# 3V3Primary.net
KiCad netlist of a schematic drawn in Altium Designer
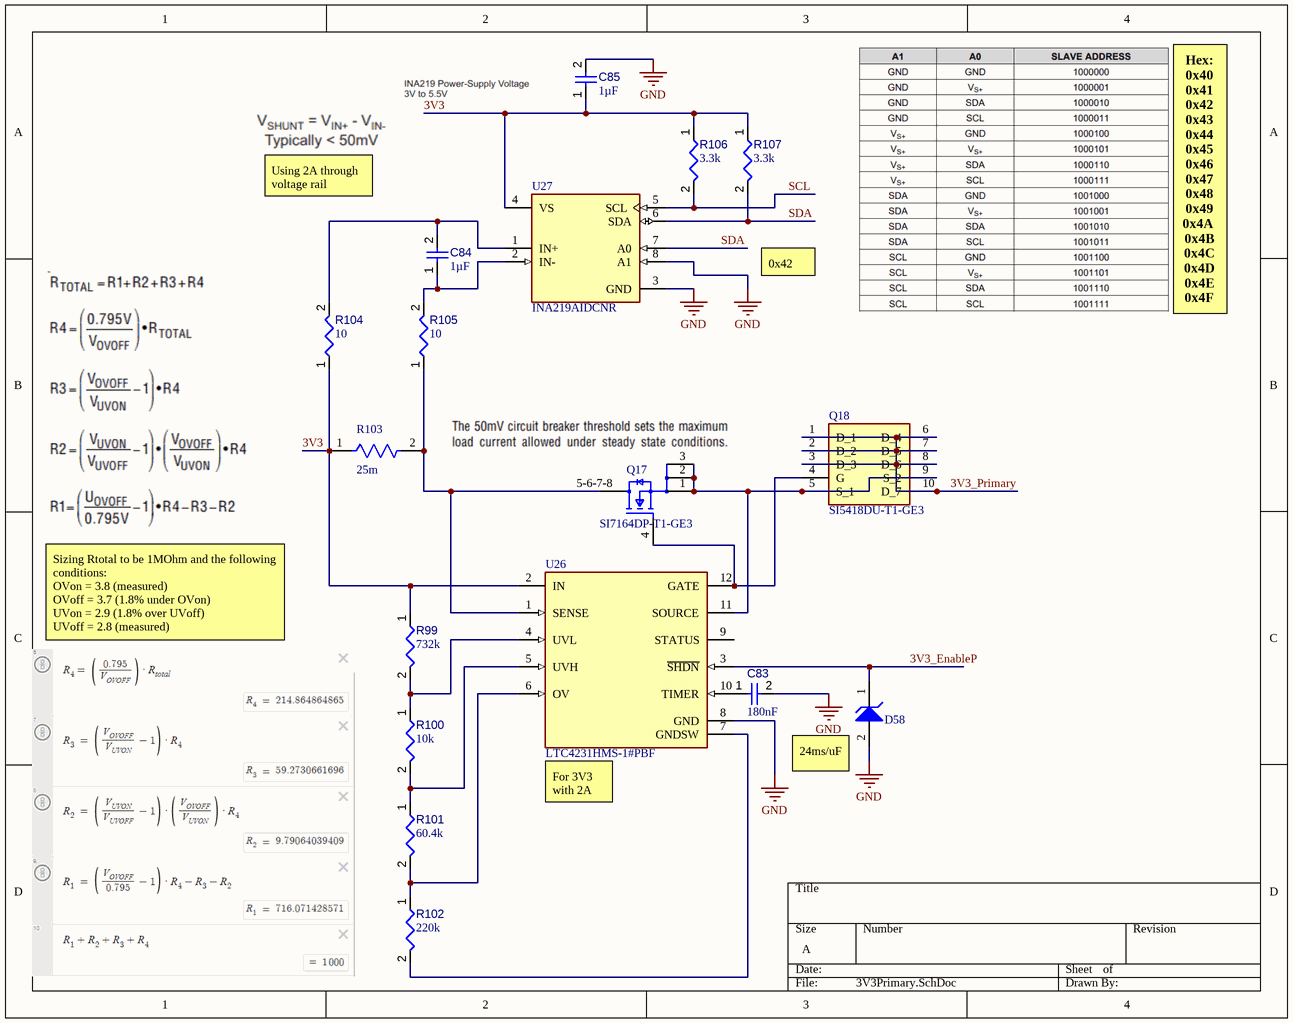
[diagram p0: 3V3Primary.SchDoc]

(export (version "E")
  (design (tool "Eeschema 10.0.6"))
  (components
    (comp (ref "C83")
      (value "180nF")
      (footprint "FP-C0805C-DN-IPC_A")
      (fields (field (name "Comment") "C0805C184K5RACTU"))
      (libsource (lib "UGA SSRL Hardware Team") (part "CAP-NP-2"))
    )
    (comp (ref "C84")
      (value "1µF")
      (footprint "CAPC1608X90X40LL10T20")
      (description "Chip Capacitor, 1 uF, +/- 10%, 25 V, 0603 (1608 Metric)")
      (fields (field (name "TOLERANCE") "10%") (field (name "Comment") "Capacitor 1 uF +/- 10% 25 V 0603"))
      (libsource (lib "UGA SSRL Hardware Team") (part "CAP-NP-2"))
    )
    (comp (ref "C85")
      (value "1µF")
      (footprint "CAPC1608X90X35ML15T15")
      (description "Chip Capacitor, 1 uF, +/- 10%, 16 V, 0603 (1608 Metric)")
      (fields (field (name "TOLERANCE") "10%") (field (name "Comment") "Capacitor 1uF +/- 10% 16V 0603"))
      (libsource (lib "UGA SSRL Hardware Team") (part "CAP-NP-2"))
    )
    (comp (ref "D58")
      (value "MM3Z3V6T1G")
      (footprint "ONSC-SOD-323-2-477-02_V")
      (description "Zener Voltage Regulator, 300 mW, 2-Pin SOD-323, Pb-Free, Tape and Reel")
      (fields (field (name "MANUFACTURER") "On Semiconductor"))
      (libsource (lib "Altium Content Vault") (part "ONSC-K1A2-2"))
    )
    (comp (ref "Q17")
      (value "SI7164DP-T1-GE3")
      (footprint "Vishay_S17-0173-SINGLE_MFG")
      (libsource (lib "UGA SSRL Hardware Team") (part "SI7164DP-T1-GE3"))
    )
    (comp (ref "Q18")
      (value "SI5418DU-T1-GE3")
      (footprint "SI5418DU-T1-GE3-Footprint-1")
      (libsource (lib "UGA SSRL Hardware Team") (part "SI5418DU-T1-GE3-Symbol-1"))
    )
    (comp (ref "R99")
      (value "732k")
      (footprint "FP-CR0805-IPC_A")
      (fields
        (field (name "POWER") "125mW")
        (field (name "TOLERANCE") "1%")
        (field (name "Comment") "CR0805-FX-7323ELF")
      )
      (libsource (lib "UGA SSRL Hardware Team") (part "RES-2"))
    )
    (comp (ref "R100")
      (value "10k")
      (footprint "RESC1005X40X25ML05T05")
      (description "Chip Resistor, 10 KOhm, +/- 1%, 0.1 W, -55 to 155 degC, 0402 (1005 Metric)")
      (fields (field (name "TOLERANCE") "1%") (field (name "POWER") "100mW"))
      (libsource (lib "UGA SSRL Hardware Team") (part "RES-2"))
    )
    (comp (ref "R101")
      (value "60.4k")
      (footprint "RESC1005X40X25NL05T10")
      (fields
        (field (name "TOLERANCE") "1%")
        (field (name "POWER") "62.5mW")
        (field (name "Comment") "RC0402FR-0760K4L")
      )
      (libsource (lib "UGA SSRL Hardware Team") (part "RES-2"))
    )
    (comp (ref "R102")
      (value "220k")
      (footprint "FP-ESR01-IPC_C")
      (fields
        (field (name "POWER") "200mW")
        (field (name "TOLERANCE") "5%")
        (field (name "Comment") "ESR01MZPJ224")
      )
      (libsource (lib "UGA SSRL Hardware Team") (part "RES-2"))
    )
    (comp (ref "R103")
      (value "CSR1206FK25L0")
      (footprint "FP-CSR1206-IPC_C")
      (description "General Purpose Thick Film Chip Resistor, 1206, 25mΩ, 1%, 0.5W")
      (fields (field (name "RESISTANCE") "25m") (field (name "TOLERANCE") "1%"))
      (libsource (lib "Altium Content Vault") (part "1029c3af85768c4190bb7ad29bc67b5"))
    )
    (comp (ref "R104")
      (value "10")
      (footprint "RESC0402(1005)_L")
      (description "Chip Resistor, 10 Ohms, +/-1 %, 63 mW, -55 to 155 degC, 0402")
      (fields (field (name "TOLERANCE") "1%") (field (name "POWER") "63mW"))
      (libsource (lib "UGA SSRL Hardware Team") (part "RES-2"))
    )
    (comp (ref "R105")
      (value "10")
      (footprint "RESC0402(1005)_L")
      (description "Chip Resistor, 10 Ohms, +/-1 %, 63 mW, -55 to 155 degC, 0402")
      (fields (field (name "TOLERANCE") "1%") (field (name "POWER") "63mW"))
      (libsource (lib "UGA SSRL Hardware Team") (part "RES-2"))
    )
    (comp (ref "R106")
      (value "3.3k")
      (footprint "FP-CRCW1210-e3-IPC_C")
      (fields
        (field (name "TOLERANCE") "5%")
        (field (name "POWER") "500mW")
        (field (name "Comment") "CRCW12103K30JNEA")
      )
      (libsource (lib "UGA SSRL Hardware Team") (part "RES-2"))
    )
    (comp (ref "R107")
      (value "3.3k")
      (footprint "FP-CRCW1210-e3-IPC_C")
      (fields
        (field (name "TOLERANCE") "5%")
        (field (name "POWER") "500mW")
        (field (name "Comment") "CRCW12103K30JNEA")
      )
      (libsource (lib "UGA SSRL Hardware Team") (part "RES-2"))
    )
    (comp (ref "U26")
      (value "LTC4231HMS-1#PBF")
      (footprint "FP-MS-12-05-08-1668-MFG")
      (description "IC HOT SWAP CTRLR GP 12MSOP")
      (libsource (lib "Altium Content Vault") (part "22a006f8750c3b6cd4295fbd2c2f62c"))
    )
    (comp (ref "U27")
      (value "INA219AIDCNR")
      (footprint "FP-DCN0008A-IPC_A")
      (description "Power Supply Support Circuit, Fixed, 2 Channel, 2V, PDSO8")
      (libsource (lib "UGA SSRL Hardware Team") (part "e16934b8ef90d0e345b266f0ae9cd81"))
    )
  )
  (nets
    (net (code "1") (name "/3V3") (class "Default")
      (node (ref "C85") (pin "1") (pinfunction "1_1") (pintype "passive"))
      (node (ref "R103") (pin "1") (pinfunction "1_1") (pintype "passive"))
      (node (ref "R104") (pin "1") (pinfunction "1_1") (pintype "passive"))
      (node (ref "R106") (pin "1") (pinfunction "1_1") (pintype "passive"))
      (node (ref "R107") (pin "1") (pinfunction "1_1") (pintype "passive"))
      (node (ref "R99") (pin "1") (pinfunction "1_1") (pintype "passive"))
      (node (ref "U26") (pin "2") (pinfunction "IN_2") (pintype "power_in"))
      (node (ref "U27") (pin "4") (pinfunction "VS_4") (pintype "power_in"))
    )
    (net (code "2") (name "/3V3_EnableP") (class "Default")
      (node (ref "D58") (pin "1") (pinfunction "K_1") (pintype "passive"))
      (node (ref "U26") (pin "3") (pinfunction "~{SHDN}_3") (pintype "input"))
    )
    (net (code "3") (name "/3V3_Primary") (class "Default")
      (node (ref "Q18") (pin "1") (pinfunction "D_1_1") (pintype "passive"))
      (node (ref "Q18") (pin "10") (pinfunction "D_7_10") (pintype "passive"))
      (node (ref "Q18") (pin "2") (pinfunction "D_2_2") (pintype "passive"))
      (node (ref "Q18") (pin "3") (pinfunction "D_3_3") (pintype "passive"))
      (node (ref "Q18") (pin "6") (pinfunction "D_4_6") (pintype "passive"))
      (node (ref "Q18") (pin "7") (pinfunction "D_5_7") (pintype "passive"))
      (node (ref "Q18") (pin "8") (pinfunction "D_6_8") (pintype "passive"))
    )
    (net (code "4") (name "/SCL") (class "Default")
      (node (ref "R106") (pin "2") (pinfunction "2_2") (pintype "passive"))
      (node (ref "U27") (pin "5") (pinfunction "SCL_5") (pintype "input"))
    )
    (net (code "5") (name "/SDA") (class "Default")
      (node (ref "R107") (pin "2") (pinfunction "2_2") (pintype "passive"))
      (node (ref "U27") (pin "6") (pinfunction "SDA_6") (pintype "bidirectional"))
      (node (ref "U27") (pin "7") (pinfunction "A0_7") (pintype "input"))
    )
    (net (code "6") (name "GND") (class "Default")
      (node (ref "C83") (pin "2") (pinfunction "2_2") (pintype "passive"))
      (node (ref "C85") (pin "2") (pinfunction "2_2") (pintype "passive"))
      (node (ref "D58") (pin "2") (pinfunction "A_2") (pintype "passive"))
      (node (ref "U26") (pin "8") (pinfunction "GND_8") (pintype "power_in"))
      (node (ref "U27") (pin "3") (pinfunction "GND_3") (pintype "power_in"))
      (node (ref "U27") (pin "8") (pinfunction "A1_8") (pintype "input"))
    )
    (net (code "7") (name "Net-(Q17-D)") (class "Default")
      (node (ref "Q17") (pin "5-6-7-8") (pinfunction "D_5-6-7-8") (pintype "passive"))
      (node (ref "R103") (pin "2") (pinfunction "2_2") (pintype "passive"))
      (node (ref "R105") (pin "1") (pinfunction "1_1") (pintype "passive"))
      (node (ref "U26") (pin "1") (pinfunction "SENSE_1") (pintype "input"))
    )
    (net (code "8") (name "Net-(Q17-G)") (class "Default")
      (node (ref "Q17") (pin "4") (pinfunction "G_4") (pintype "passive"))
      (node (ref "Q18") (pin "4") (pinfunction "G_4") (pintype "passive"))
      (node (ref "U26") (pin "12") (pinfunction "GATE_12") (pintype "passive"))
    )
    (net (code "9") (name "Net-(Q18-S_1)") (class "Default")
      (node (ref "Q17") (pin "1") (pinfunction "S_1") (pintype "passive"))
      (node (ref "Q17") (pin "2") (pinfunction "S_2") (pintype "passive"))
      (node (ref "Q17") (pin "3") (pinfunction "S_3") (pintype "passive"))
      (node (ref "Q18") (pin "5") (pinfunction "S_1_5") (pintype "passive"))
      (node (ref "Q18") (pin "9") (pinfunction "S_2_9") (pintype "passive"))
      (node (ref "U26") (pin "11") (pinfunction "SOURCE_11") (pintype "passive"))
    )
    (net (code "10") (name "Net-(U26-GNDSW)") (class "Default")
      (node (ref "R102") (pin "2") (pinfunction "2_2") (pintype "passive"))
      (node (ref "U26") (pin "7") (pinfunction "GNDSW_7") (pintype "power_in"))
    )
    (net (code "11") (name "Net-(U26-OV)") (class "Default")
      (node (ref "R101") (pin "2") (pinfunction "2_2") (pintype "passive"))
      (node (ref "R102") (pin "1") (pinfunction "1_1") (pintype "passive"))
      (node (ref "U26") (pin "6") (pinfunction "OV_6") (pintype "input"))
    )
    (net (code "12") (name "Net-(U26-TIMER)") (class "Default")
      (node (ref "C83") (pin "1") (pinfunction "1_1") (pintype "passive"))
      (node (ref "U26") (pin "10") (pinfunction "TIMER_10") (pintype "input"))
    )
    (net (code "13") (name "Net-(U26-UVH)") (class "Default")
      (node (ref "R100") (pin "2") (pinfunction "2_2") (pintype "passive"))
      (node (ref "R101") (pin "1") (pinfunction "1_1") (pintype "passive"))
      (node (ref "U26") (pin "5") (pinfunction "UVH_5") (pintype "input"))
    )
    (net (code "14") (name "Net-(U26-UVL)") (class "Default")
      (node (ref "R100") (pin "1") (pinfunction "1_1") (pintype "passive"))
      (node (ref "R99") (pin "2") (pinfunction "2_2") (pintype "passive"))
      (node (ref "U26") (pin "4") (pinfunction "UVL_4") (pintype "input"))
    )
    (net (code "15") (name "Net-(U27-IN+)") (class "Default")
      (node (ref "C84") (pin "2") (pinfunction "2_2") (pintype "passive"))
      (node (ref "R104") (pin "2") (pinfunction "2_2") (pintype "passive"))
      (node (ref "U27") (pin "1") (pinfunction "IN+_1") (pintype "passive"))
    )
    (net (code "16") (name "Net-(U27-IN-)") (class "Default")
      (node (ref "C84") (pin "1") (pinfunction "1_1") (pintype "passive"))
      (node (ref "R105") (pin "2") (pinfunction "2_2") (pintype "passive"))
      (node (ref "U27") (pin "2") (pinfunction "IN-_2") (pintype "input"))
    )
    (net (code "17") (name "unconnected-(U26-STATUS-Pad9)") (class "Default")
      (node (ref "U26") (pin "9") (pinfunction "STATUS_9") (pintype "open_collector"))
    )
  )
)
